# Esquematico_Germinador.net
KiCad netlist of a schematic drawn in EAGLE
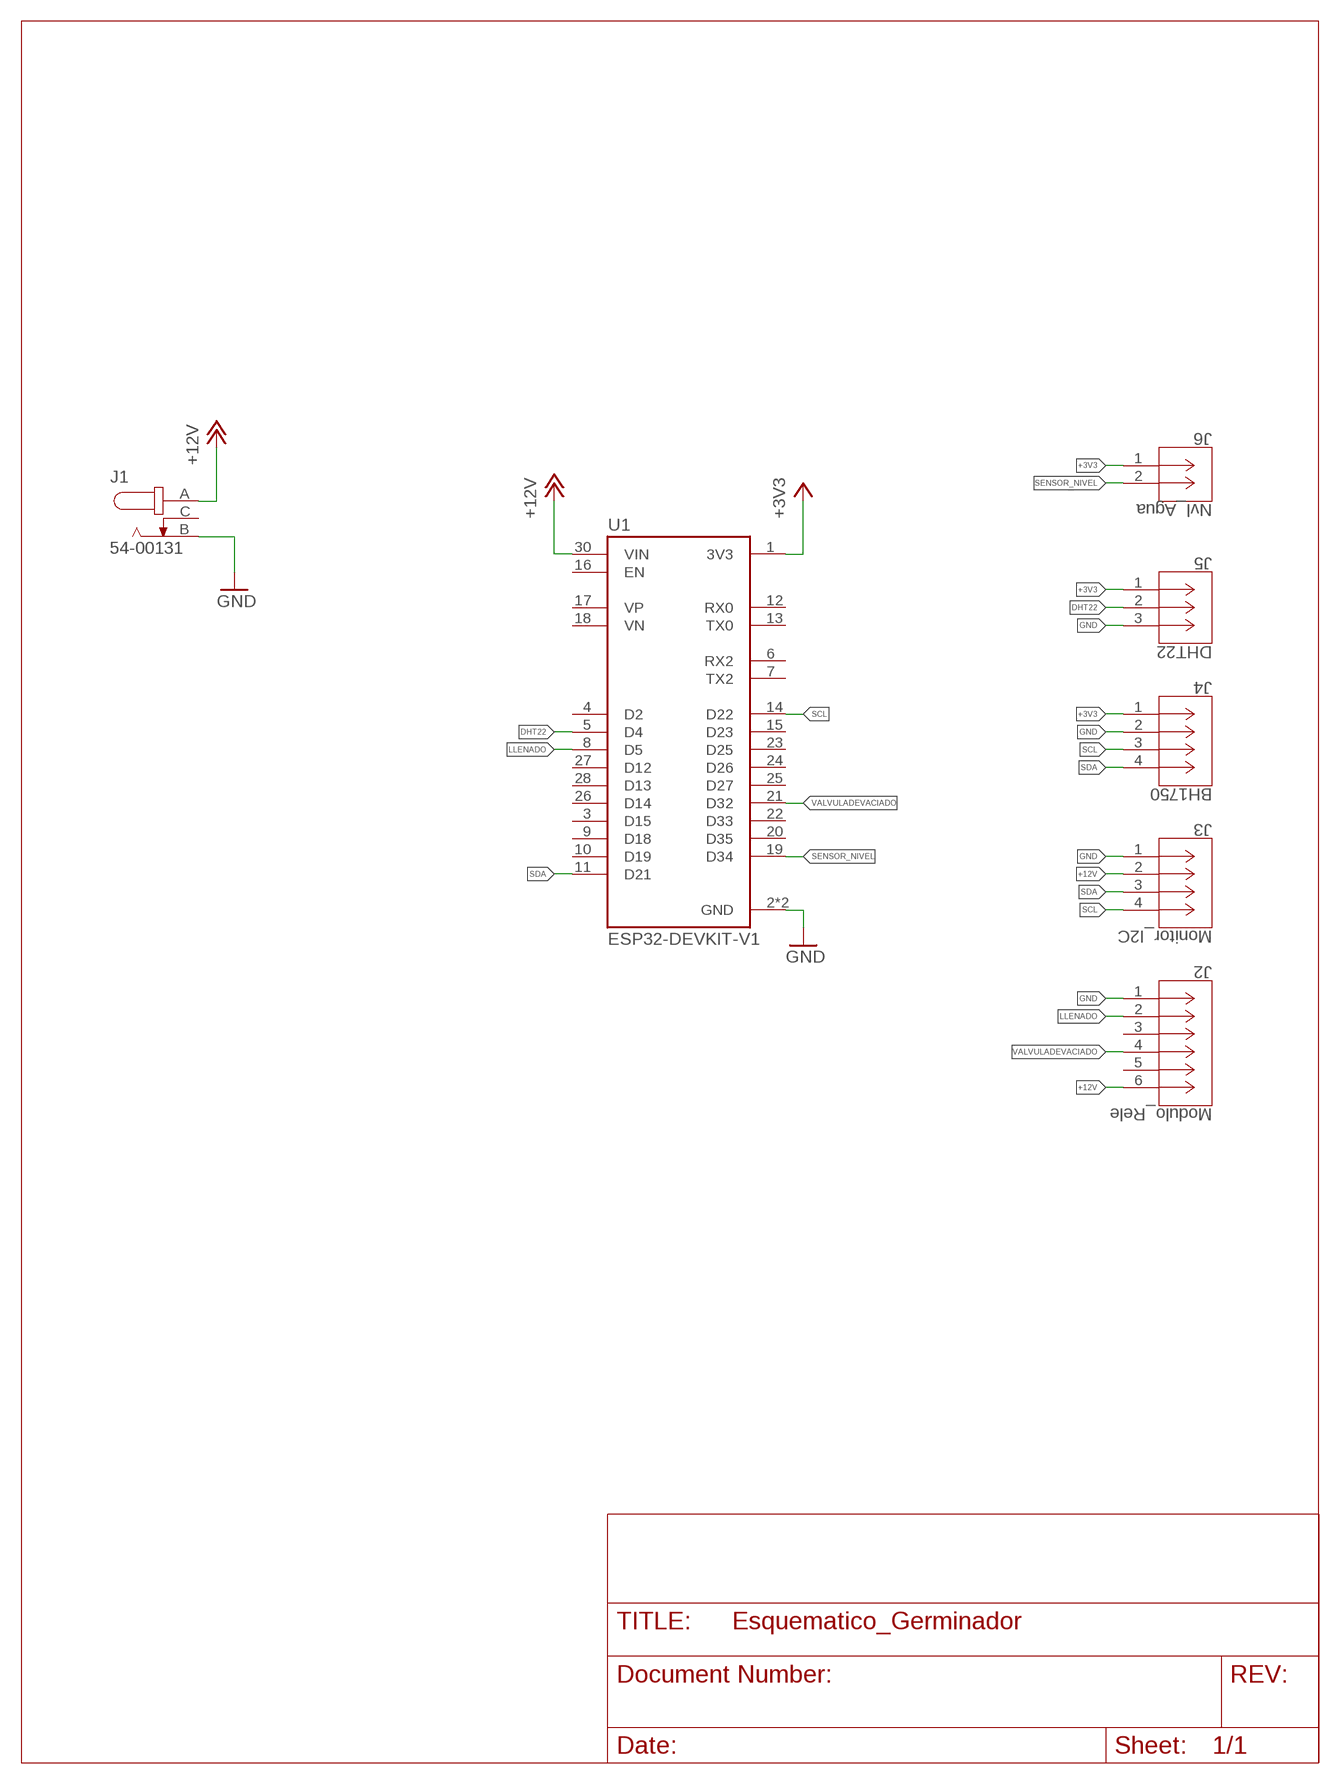
[diagram p0: schematic, sheet 1]

(export (version "E")
  (design (tool "Eeschema 10.0.6"))
  (components
    (comp (ref "J1")
      (value "54-00131")
      (footprint "eagle-import:54-00131")
      (libsource (lib "eagle-import") (part "54-00131"))
    )
    (comp (ref "J2")
      (value "Modulo_Rele")
      (footprint "eagle-import:CONN_B6B-XH-A(LF)(SN)_JST")
      (fields
        (field (name "MANUFACTURER_PART_NUMBER") "B6B-XH-A(LF)(SN)")
        (field (name "COPYRIGHT") "Copyright (C) 2018 Accelerated Designs. All rights reserved")
      )
      (libsource (lib "eagle-import") (part "B6B-XH-A(LF)(SN)"))
    )
    (comp (ref "J3")
      (value "Monitor_I2C")
      (footprint "eagle-import:CONN_B4B-XH-A_(LF)(SN)_JST")
      (fields
        (field (name "MANUFACTURER_PART_NUMBER") "B4B-XH-A (LF)(SN)")
        (field (name "COPYRIGHT") "Copyright (C) 2018 Accelerated Designs. All rights reserved")
      )
      (libsource (lib "eagle-import") (part "B4B-XH-A_(LF)(SN)"))
    )
    (comp (ref "J4")
      (value "BH1750")
      (footprint "eagle-import:CONN_B4B-XH-A_(LF)(SN)_JST")
      (fields
        (field (name "MANUFACTURER_PART_NUMBER") "B4B-XH-A (LF)(SN)")
        (field (name "COPYRIGHT") "Copyright (C) 2018 Accelerated Designs. All rights reserved")
      )
      (libsource (lib "eagle-import") (part "B4B-XH-A_(LF)(SN)"))
    )
    (comp (ref "J5")
      (value "DHT22")
      (footprint "eagle-import:CONN_B3B-XH-A_JST")
      (fields
        (field (name "MANUFACTURER_PART_NUMBER") "B3B-XH-A(LF)(SN)")
        (field (name "COPYRIGHT") "Copyright (C) 2018 Accelerated Designs. All rights reserved")
      )
      (libsource (lib "eagle-import") (part "B3B-XH-A(LF)(SN)"))
    )
    (comp (ref "J6")
      (value "Nvl_Agua")
      (footprint "eagle-import:CONN_B2B-XH-A(LF)(SN)_JST")
      (fields
        (field (name "MANUFACTURER_PART_NUMBER") "B2B-XH-A(LF)(SN)")
        (field (name "COPYRIGHT") "Copyright (C) 2018 Accelerated Designs. All rights reserved")
      )
      (libsource (lib "eagle-import") (part "B2B-XH-A(LF)(SN)"))
    )
    (comp (ref "U1")
      (value "ESP32-DEVKIT-V1")
      (footprint "eagle-import:MODULE_ESP32_DEVKIT_V1")
      (fields (field (name "MF") "Do it"))
      (libsource (lib "eagle-import") (part "ESP32-DEVKIT-V1"))
    )
  )
  (nets
    (net (code "1") (name "+3V3") (class "Default")
      (node (ref "J4") (pin "1") (pinfunction "1_1") (pintype "passive"))
      (node (ref "J5") (pin "1") (pinfunction "1_1") (pintype "passive"))
      (node (ref "J6") (pin "1") (pinfunction "1_1") (pintype "passive"))
      (node (ref "U1") (pin "1") (pinfunction "3V3_1") (pintype "output"))
    )
    (net (code "2") (name "+12V") (class "Default")
      (node (ref "J1") (pin "A") (pinfunction "A_A") (pintype "passive"))
      (node (ref "J2") (pin "6") (pinfunction "6_6") (pintype "passive"))
      (node (ref "J3") (pin "2") (pinfunction "2_2") (pintype "passive"))
      (node (ref "U1") (pin "30") (pinfunction "VIN_30") (pintype "input"))
    )
    (net (code "3") (name "DHT22") (class "Default")
      (node (ref "J5") (pin "2") (pinfunction "2_2") (pintype "passive"))
      (node (ref "U1") (pin "5") (pinfunction "D4_5") (pintype "bidirectional"))
    )
    (net (code "4") (name "GND") (class "Default")
      (node (ref "J1") (pin "B") (pinfunction "B_B") (pintype "passive"))
      (node (ref "J2") (pin "1") (pinfunction "1_1") (pintype "passive"))
      (node (ref "J3") (pin "1") (pinfunction "1_1") (pintype "passive"))
      (node (ref "J4") (pin "2") (pinfunction "2_2") (pintype "passive"))
      (node (ref "J5") (pin "3") (pinfunction "3_3") (pintype "passive"))
      (node (ref "U1") (pin "2") (pinfunction "GND_2") (pintype "power_in"))
      (node (ref "U1") (pin "29") (pinfunction "GND_29") (pintype "power_in"))
    )
    (net (code "5") (name "LLENADO") (class "Default")
      (node (ref "J2") (pin "2") (pinfunction "2_2") (pintype "passive"))
      (node (ref "U1") (pin "8") (pinfunction "D5_8") (pintype "bidirectional"))
    )
    (net (code "6") (name "SCL") (class "Default")
      (node (ref "J3") (pin "4") (pinfunction "4_4") (pintype "passive"))
      (node (ref "J4") (pin "3") (pinfunction "3_3") (pintype "passive"))
      (node (ref "U1") (pin "14") (pinfunction "D22_14") (pintype "bidirectional"))
    )
    (net (code "7") (name "SDA") (class "Default")
      (node (ref "J3") (pin "3") (pinfunction "3_3") (pintype "passive"))
      (node (ref "J4") (pin "4") (pinfunction "4_4") (pintype "passive"))
      (node (ref "U1") (pin "11") (pinfunction "D21_11") (pintype "bidirectional"))
    )
    (net (code "8") (name "SENSOR_NIVEL") (class "Default")
      (node (ref "J6") (pin "2") (pinfunction "2_2") (pintype "passive"))
      (node (ref "U1") (pin "19") (pinfunction "D34_19") (pintype "bidirectional"))
    )
    (net (code "9") (name "VALVULADEVACIADO") (class "Default")
      (node (ref "J2") (pin "4") (pinfunction "4_4") (pintype "passive"))
      (node (ref "U1") (pin "21") (pinfunction "D32_21") (pintype "bidirectional"))
    )
    (net (code "10") (name "unconnected-(J1-PadC)") (class "Default")
      (node (ref "J1") (pin "C") (pinfunction "C_C") (pintype "passive"))
    )
    (net (code "11") (name "unconnected-(J2-Pad3)") (class "Default")
      (node (ref "J2") (pin "3") (pinfunction "3_3") (pintype "passive"))
    )
    (net (code "12") (name "unconnected-(J2-Pad5)") (class "Default")
      (node (ref "J2") (pin "5") (pinfunction "5_5") (pintype "passive"))
    )
    (net (code "13") (name "unconnected-(U1-D2-Pad4)") (class "Default")
      (node (ref "U1") (pin "4") (pinfunction "D2_4") (pintype "bidirectional"))
    )
    (net (code "14") (name "unconnected-(U1-D12-Pad27)") (class "Default")
      (node (ref "U1") (pin "27") (pinfunction "D12_27") (pintype "bidirectional"))
    )
    (net (code "15") (name "unconnected-(U1-D13-Pad28)") (class "Default")
      (node (ref "U1") (pin "28") (pinfunction "D13_28") (pintype "bidirectional"))
    )
    (net (code "16") (name "unconnected-(U1-D14-Pad26)") (class "Default")
      (node (ref "U1") (pin "26") (pinfunction "D14_26") (pintype "bidirectional"))
    )
    (net (code "17") (name "unconnected-(U1-D15-Pad3)") (class "Default")
      (node (ref "U1") (pin "3") (pinfunction "D15_3") (pintype "bidirectional"))
    )
    (net (code "18") (name "unconnected-(U1-D18-Pad9)") (class "Default")
      (node (ref "U1") (pin "9") (pinfunction "D18_9") (pintype "bidirectional"))
    )
    (net (code "19") (name "unconnected-(U1-D19-Pad10)") (class "Default")
      (node (ref "U1") (pin "10") (pinfunction "D19_10") (pintype "bidirectional"))
    )
    (net (code "20") (name "unconnected-(U1-D23-Pad15)") (class "Default")
      (node (ref "U1") (pin "15") (pinfunction "D23_15") (pintype "bidirectional"))
    )
    (net (code "21") (name "unconnected-(U1-D25-Pad23)") (class "Default")
      (node (ref "U1") (pin "23") (pinfunction "D25_23") (pintype "bidirectional"))
    )
    (net (code "22") (name "unconnected-(U1-D26-Pad24)") (class "Default")
      (node (ref "U1") (pin "24") (pinfunction "D26_24") (pintype "bidirectional"))
    )
    (net (code "23") (name "unconnected-(U1-D27-Pad25)") (class "Default")
      (node (ref "U1") (pin "25") (pinfunction "D27_25") (pintype "bidirectional"))
    )
    (net (code "24") (name "unconnected-(U1-D33-Pad22)") (class "Default")
      (node (ref "U1") (pin "22") (pinfunction "D33_22") (pintype "bidirectional"))
    )
    (net (code "25") (name "unconnected-(U1-D35-Pad20)") (class "Default")
      (node (ref "U1") (pin "20") (pinfunction "D35_20") (pintype "bidirectional"))
    )
    (net (code "26") (name "unconnected-(U1-EN-Pad16)") (class "Default")
      (node (ref "U1") (pin "16") (pinfunction "EN_16") (pintype "input"))
    )
    (net (code "27") (name "unconnected-(U1-RX0-Pad12)") (class "Default")
      (node (ref "U1") (pin "12") (pinfunction "RX0_12") (pintype "input"))
    )
    (net (code "28") (name "unconnected-(U1-RX2-Pad6)") (class "Default")
      (node (ref "U1") (pin "6") (pinfunction "RX2_6") (pintype "input"))
    )
    (net (code "29") (name "unconnected-(U1-TX0-Pad13)") (class "Default")
      (node (ref "U1") (pin "13") (pinfunction "TX0_13") (pintype "output"))
    )
    (net (code "30") (name "unconnected-(U1-TX2-Pad7)") (class "Default")
      (node (ref "U1") (pin "7") (pinfunction "TX2_7") (pintype "output"))
    )
    (net (code "31") (name "unconnected-(U1-VN-Pad18)") (class "Default")
      (node (ref "U1") (pin "18") (pinfunction "VN_18") (pintype "bidirectional"))
    )
    (net (code "32") (name "unconnected-(U1-VP-Pad17)") (class "Default")
      (node (ref "U1") (pin "17") (pinfunction "VP_17") (pintype "bidirectional"))
    )
  )
)
